# Pico_36Pin_Keyboard.net
KiCad netlist of a schematic drawn in EAGLE
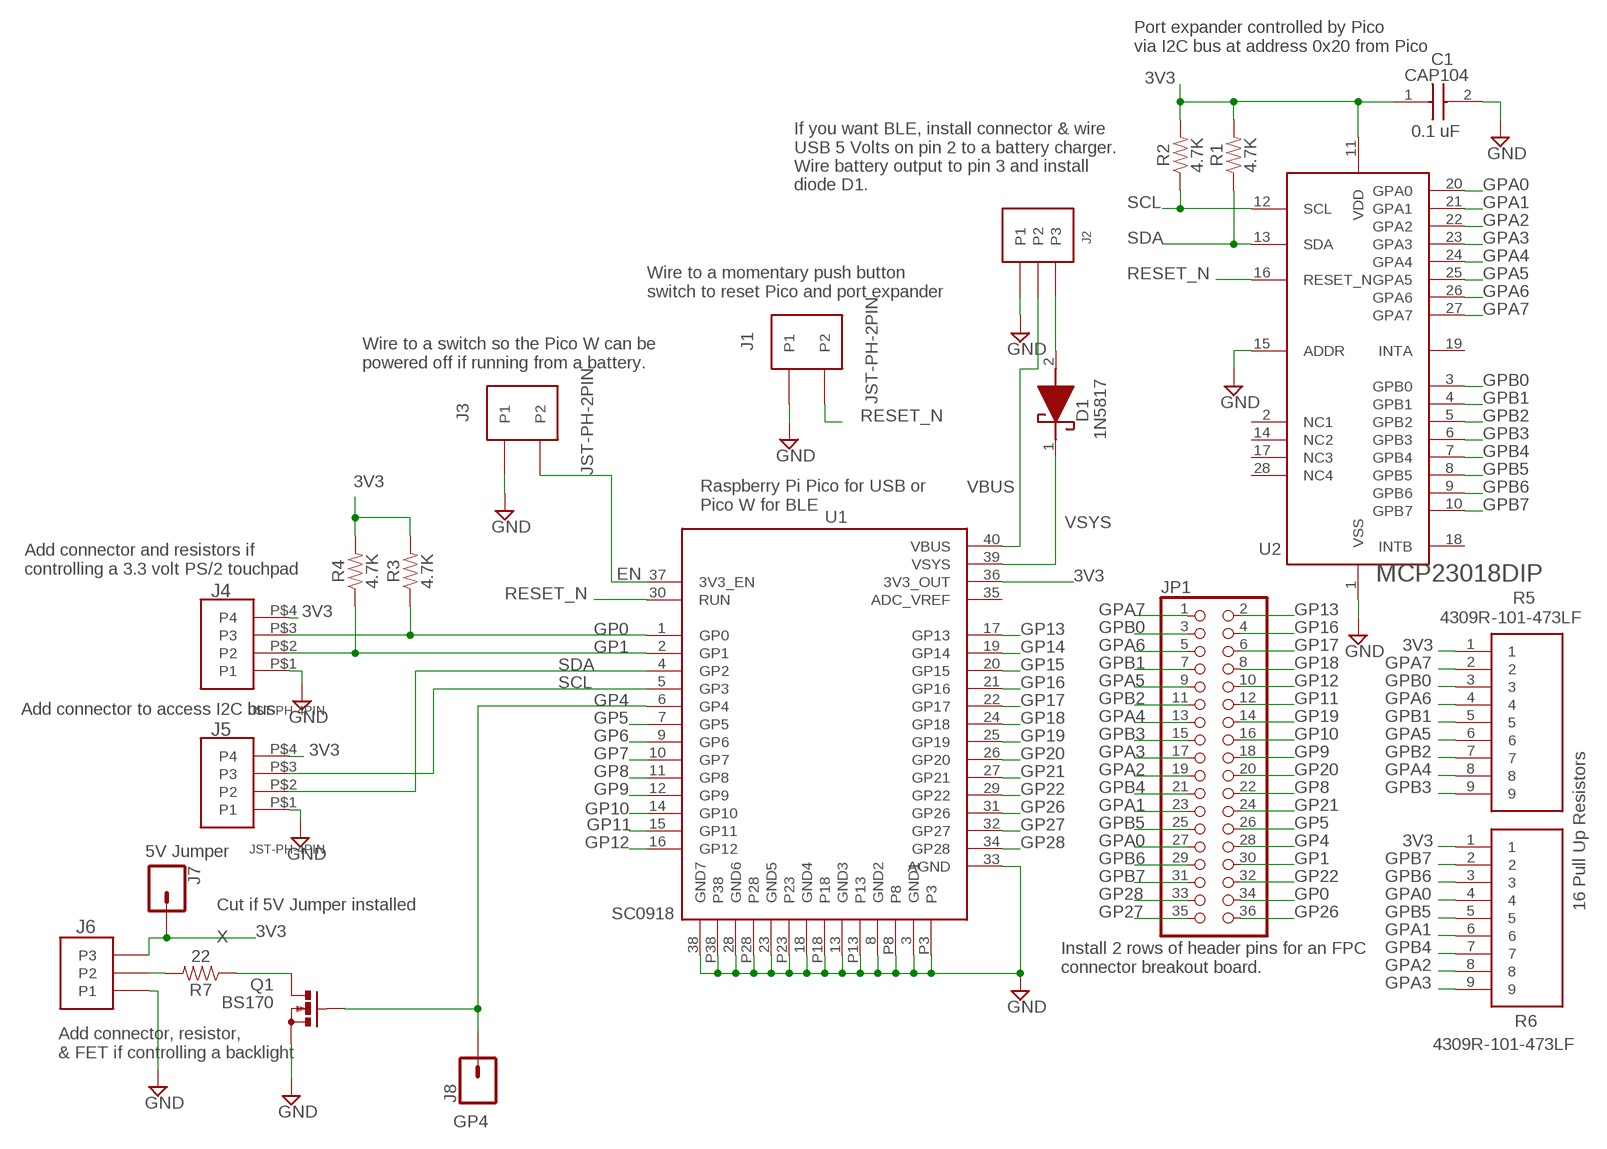
[diagram p0: schematic, sheet 1]

(export (version "E")
  (design (tool "Eeschema 10.0.6"))
  (components
    (comp (ref "C1")
      (value "CAP104")
      (footprint "eagle-import:CAP104")
      (libsource (lib "eagle-import") (part "CAP104"))
    )
    (comp (ref "D1")
      (value "1N5817")
      (footprint "eagle-import:DIOAD1410W86L470D235")
      (fields (field (name "MOUSER_PART_NUMBER") "821-1N5817"))
      (libsource (lib "eagle-import") (part "1N5817"))
    )
    (comp (ref "J1")
      (value "JST-PH-2PIN")
      (footprint "eagle-import:JST-PH-2PIN")
      (libsource (lib "eagle-import") (part "JST-PH-2PIN"))
    )
    (comp (ref "J2")
      (value "JST-PH-3PIN")
      (footprint "eagle-import:JST-PH-3PIN")
      (libsource (lib "eagle-import") (part "JST-PH-3PIN"))
    )
    (comp (ref "J3")
      (value "JST-PH-2PIN")
      (footprint "eagle-import:JST-PH-2PIN")
      (libsource (lib "eagle-import") (part "JST-PH-2PIN"))
    )
    (comp (ref "J4")
      (value "JST-PH-4PIN")
      (footprint "eagle-import:JST-PH-4PIN")
      (libsource (lib "eagle-import") (part "JST-PH-4PIN"))
    )
    (comp (ref "J5")
      (value "JST-PH-4PIN")
      (footprint "eagle-import:JST-PH-4PIN")
      (libsource (lib "eagle-import") (part "JST-PH-4PIN"))
    )
    (comp (ref "J6")
      (value "JST-PH-3PIN")
      (footprint "eagle-import:JST-PH-3PIN")
      (libsource (lib "eagle-import") (part "JST-PH-3PIN"))
    )
    (comp (ref "J7")
      (value "CONN_01")
      (footprint "eagle-import:1X01")
      (libsource (lib "eagle-import") (part "CONN_01"))
    )
    (comp (ref "J8")
      (value "CONN_01")
      (footprint "eagle-import:1X01")
      (libsource (lib "eagle-import") (part "CONN_01"))
    )
    (comp (ref "JP1")
      (value "PINHD-2X18")
      (footprint "eagle-import:2X18")
      (libsource (lib "eagle-import") (part "PINHD-2X18"))
    )
    (comp (ref "Q1")
      (value "BS170")
      (footprint "eagle-import:SOT54E")
      (libsource (lib "eagle-import") (part "BS170"))
    )
    (comp (ref "R1")
      (value "4.7K")
      (footprint "eagle-import:AXIAL-0.3")
      (libsource (lib "eagle-import") (part "RESISTOR_AXIAL"))
    )
    (comp (ref "R2")
      (value "4.7K")
      (footprint "eagle-import:AXIAL-0.3")
      (libsource (lib "eagle-import") (part "RESISTOR_AXIAL"))
    )
    (comp (ref "R3")
      (value "4.7K")
      (footprint "eagle-import:AXIAL-0.3")
      (libsource (lib "eagle-import") (part "RESISTOR_AXIAL"))
    )
    (comp (ref "R4")
      (value "4.7K")
      (footprint "eagle-import:AXIAL-0.3")
      (libsource (lib "eagle-import") (part "RESISTOR_AXIAL"))
    )
    (comp (ref "R5")
      (value "4309R-101-473LF")
      (footprint "eagle-import:4309R-101-473LF")
      (libsource (lib "eagle-import") (part "4309R-101-473LF"))
    )
    (comp (ref "R6")
      (value "4309R-101-473LF")
      (footprint "eagle-import:4309R-101-473LF")
      (libsource (lib "eagle-import") (part "4309R-101-473LF"))
    )
    (comp (ref "R7")
      (value "22")
      (footprint "eagle-import:AXIAL-0.3")
      (libsource (lib "eagle-import") (part "RESISTOR_AXIAL"))
    )
    (comp (ref "U1")
      (value "SC0918")
      (footprint "eagle-import:MODULE_SC0918")
      (fields (field (name "MF") "Raspberry Pi"))
      (libsource (lib "eagle-import") (part "SC0918"))
    )
    (comp (ref "U2")
      (value "MCP23018DIP")
      (footprint "eagle-import:MCP23018DIP")
      (libsource (lib "eagle-import") (part "MCP23018DIP"))
    )
  )
  (nets
    (net (code "1") (name "/3V3") (class "Default")
      (node (ref "C1") (pin "1") (pinfunction "1_1") (pintype "bidirectional"))
      (node (ref "J4") (pin "P$4") (pinfunction "P4_P$4") (pintype "bidirectional"))
      (node (ref "J5") (pin "P$4") (pinfunction "P4_P$4") (pintype "bidirectional"))
      (node (ref "J6") (pin "P$3") (pinfunction "P3_P$3") (pintype "bidirectional"))
      (node (ref "J7") (pin "1") (pinfunction "1_1") (pintype "passive"))
      (node (ref "R1") (pin "P$2") (pinfunction "2_P$2") (pintype "passive"))
      (node (ref "R2") (pin "P$2") (pinfunction "2_P$2") (pintype "passive"))
      (node (ref "R3") (pin "P$2") (pinfunction "2_P$2") (pintype "passive"))
      (node (ref "R4") (pin "P$2") (pinfunction "2_P$2") (pintype "passive"))
      (node (ref "R5") (pin "1") (pinfunction "1_1") (pintype "bidirectional"))
      (node (ref "R6") (pin "1") (pinfunction "1_1") (pintype "bidirectional"))
      (node (ref "U1") (pin "36") (pinfunction "3V3_OUT_36") (pintype "power_in"))
      (node (ref "U2") (pin "11") (pinfunction "VDD_11") (pintype "bidirectional"))
    )
    (net (code "2") (name "/ADC_VREF") (class "Default")
      (node (ref "U1") (pin "35") (pinfunction "ADC_VREF_35") (pintype "power_in"))
    )
    (net (code "3") (name "/EN") (class "Default")
      (node (ref "J3") (pin "P$2") (pinfunction "P2_P$2") (pintype "bidirectional"))
      (node (ref "U1") (pin "37") (pinfunction "3V3_EN_37") (pintype "input"))
    )
    (net (code "4") (name "/GP0") (class "Default")
      (node (ref "J4") (pin "P$3") (pinfunction "P3_P$3") (pintype "bidirectional"))
      (node (ref "JP1") (pin "34") (pinfunction "34_34") (pintype "passive"))
      (node (ref "R3") (pin "P$1") (pinfunction "1_P$1") (pintype "passive"))
      (node (ref "U1") (pin "1") (pinfunction "GP0_1") (pintype "bidirectional"))
    )
    (net (code "5") (name "/GP1") (class "Default")
      (node (ref "J4") (pin "P$2") (pinfunction "P2_P$2") (pintype "bidirectional"))
      (node (ref "JP1") (pin "30") (pinfunction "30_30") (pintype "passive"))
      (node (ref "R4") (pin "P$1") (pinfunction "1_P$1") (pintype "passive"))
      (node (ref "U1") (pin "2") (pinfunction "GP1_2") (pintype "bidirectional"))
    )
    (net (code "6") (name "/GP4") (class "Default")
      (node (ref "J8") (pin "1") (pinfunction "1_1") (pintype "passive"))
      (node (ref "JP1") (pin "28") (pinfunction "28_28") (pintype "passive"))
      (node (ref "Q1") (pin "G") (pinfunction "G_G") (pintype "passive"))
      (node (ref "U1") (pin "6") (pinfunction "GP4_6") (pintype "bidirectional"))
    )
    (net (code "7") (name "/GP5") (class "Default")
      (node (ref "JP1") (pin "26") (pinfunction "26_26") (pintype "passive"))
      (node (ref "U1") (pin "7") (pinfunction "GP5_7") (pintype "bidirectional"))
    )
    (net (code "8") (name "/GP6") (class "Default")
      (node (ref "U1") (pin "9") (pinfunction "GP6_9") (pintype "bidirectional"))
    )
    (net (code "9") (name "/GP7") (class "Default")
      (node (ref "U1") (pin "10") (pinfunction "GP7_10") (pintype "bidirectional"))
    )
    (net (code "10") (name "/GP8") (class "Default")
      (node (ref "JP1") (pin "22") (pinfunction "22_22") (pintype "passive"))
      (node (ref "U1") (pin "11") (pinfunction "GP8_11") (pintype "bidirectional"))
    )
    (net (code "11") (name "/GP9") (class "Default")
      (node (ref "JP1") (pin "18") (pinfunction "18_18") (pintype "passive"))
      (node (ref "U1") (pin "12") (pinfunction "GP9_12") (pintype "bidirectional"))
    )
    (net (code "12") (name "/GP10") (class "Default")
      (node (ref "JP1") (pin "16") (pinfunction "16_16") (pintype "passive"))
      (node (ref "U1") (pin "14") (pinfunction "GP10_14") (pintype "bidirectional"))
    )
    (net (code "13") (name "/GP11") (class "Default")
      (node (ref "JP1") (pin "12") (pinfunction "12_12") (pintype "passive"))
      (node (ref "U1") (pin "15") (pinfunction "GP11_15") (pintype "bidirectional"))
    )
    (net (code "14") (name "/GP12") (class "Default")
      (node (ref "JP1") (pin "10") (pinfunction "10_10") (pintype "passive"))
      (node (ref "U1") (pin "16") (pinfunction "GP12_16") (pintype "bidirectional"))
    )
    (net (code "15") (name "/GP13") (class "Default")
      (node (ref "JP1") (pin "2") (pinfunction "2_2") (pintype "passive"))
      (node (ref "U1") (pin "17") (pinfunction "GP13_17") (pintype "bidirectional"))
    )
    (net (code "16") (name "/GP14") (class "Default")
      (node (ref "U1") (pin "19") (pinfunction "GP14_19") (pintype "bidirectional"))
    )
    (net (code "17") (name "/GP15") (class "Default")
      (node (ref "U1") (pin "20") (pinfunction "GP15_20") (pintype "bidirectional"))
    )
    (net (code "18") (name "/GP16") (class "Default")
      (node (ref "JP1") (pin "4") (pinfunction "4_4") (pintype "passive"))
      (node (ref "U1") (pin "21") (pinfunction "GP16_21") (pintype "bidirectional"))
    )
    (net (code "19") (name "/GP17") (class "Default")
      (node (ref "JP1") (pin "6") (pinfunction "6_6") (pintype "passive"))
      (node (ref "U1") (pin "22") (pinfunction "GP17_22") (pintype "bidirectional"))
    )
    (net (code "20") (name "/GP18") (class "Default")
      (node (ref "JP1") (pin "8") (pinfunction "8_8") (pintype "passive"))
      (node (ref "U1") (pin "24") (pinfunction "GP18_24") (pintype "bidirectional"))
    )
    (net (code "21") (name "/GP19") (class "Default")
      (node (ref "JP1") (pin "14") (pinfunction "14_14") (pintype "passive"))
      (node (ref "U1") (pin "25") (pinfunction "GP19_25") (pintype "bidirectional"))
    )
    (net (code "22") (name "/GP20") (class "Default")
      (node (ref "JP1") (pin "20") (pinfunction "20_20") (pintype "passive"))
      (node (ref "U1") (pin "26") (pinfunction "GP20_26") (pintype "bidirectional"))
    )
    (net (code "23") (name "/GP21") (class "Default")
      (node (ref "JP1") (pin "24") (pinfunction "24_24") (pintype "passive"))
      (node (ref "U1") (pin "27") (pinfunction "GP21_27") (pintype "bidirectional"))
    )
    (net (code "24") (name "/GP22") (class "Default")
      (node (ref "JP1") (pin "32") (pinfunction "32_32") (pintype "passive"))
      (node (ref "U1") (pin "29") (pinfunction "GP22_29") (pintype "bidirectional"))
    )
    (net (code "25") (name "/GP26") (class "Default")
      (node (ref "JP1") (pin "36") (pinfunction "36_36") (pintype "passive"))
      (node (ref "U1") (pin "31") (pinfunction "GP26_31") (pintype "bidirectional"))
    )
    (net (code "26") (name "/GP27") (class "Default")
      (node (ref "JP1") (pin "35") (pinfunction "35_35") (pintype "passive"))
      (node (ref "U1") (pin "32") (pinfunction "GP27_32") (pintype "bidirectional"))
    )
    (net (code "27") (name "/GP28") (class "Default")
      (node (ref "JP1") (pin "33") (pinfunction "33_33") (pintype "passive"))
      (node (ref "U1") (pin "34") (pinfunction "GP28_34") (pintype "bidirectional"))
    )
    (net (code "28") (name "/GPA0") (class "Default")
      (node (ref "JP1") (pin "27") (pinfunction "27_27") (pintype "passive"))
      (node (ref "R6") (pin "4") (pinfunction "4_4") (pintype "bidirectional"))
      (node (ref "U2") (pin "20") (pinfunction "GPA0_20") (pintype "bidirectional"))
    )
    (net (code "29") (name "/GPA1") (class "Default")
      (node (ref "JP1") (pin "23") (pinfunction "23_23") (pintype "passive"))
      (node (ref "R6") (pin "6") (pinfunction "6_6") (pintype "bidirectional"))
      (node (ref "U2") (pin "21") (pinfunction "GPA1_21") (pintype "bidirectional"))
    )
    (net (code "30") (name "/GPA2") (class "Default")
      (node (ref "JP1") (pin "19") (pinfunction "19_19") (pintype "passive"))
      (node (ref "R6") (pin "8") (pinfunction "8_8") (pintype "bidirectional"))
      (node (ref "U2") (pin "22") (pinfunction "GPA2_22") (pintype "bidirectional"))
    )
    (net (code "31") (name "/GPA3") (class "Default")
      (node (ref "JP1") (pin "17") (pinfunction "17_17") (pintype "passive"))
      (node (ref "R6") (pin "9") (pinfunction "9_9") (pintype "bidirectional"))
      (node (ref "U2") (pin "23") (pinfunction "GPA3_23") (pintype "bidirectional"))
    )
    (net (code "32") (name "/GPA4") (class "Default")
      (node (ref "JP1") (pin "13") (pinfunction "13_13") (pintype "passive"))
      (node (ref "R5") (pin "8") (pinfunction "8_8") (pintype "bidirectional"))
      (node (ref "U2") (pin "24") (pinfunction "GPA4_24") (pintype "bidirectional"))
    )
    (net (code "33") (name "/GPA5") (class "Default")
      (node (ref "JP1") (pin "9") (pinfunction "9_9") (pintype "passive"))
      (node (ref "R5") (pin "6") (pinfunction "6_6") (pintype "bidirectional"))
      (node (ref "U2") (pin "25") (pinfunction "GPA5_25") (pintype "bidirectional"))
    )
    (net (code "34") (name "/GPA6") (class "Default")
      (node (ref "JP1") (pin "5") (pinfunction "5_5") (pintype "passive"))
      (node (ref "R5") (pin "4") (pinfunction "4_4") (pintype "bidirectional"))
      (node (ref "U2") (pin "26") (pinfunction "GPA6_26") (pintype "bidirectional"))
    )
    (net (code "35") (name "/GPA7") (class "Default")
      (node (ref "JP1") (pin "1") (pinfunction "1_1") (pintype "passive"))
      (node (ref "R5") (pin "2") (pinfunction "2_2") (pintype "bidirectional"))
      (node (ref "U2") (pin "27") (pinfunction "GPA7_27") (pintype "bidirectional"))
    )
    (net (code "36") (name "/GPB0") (class "Default")
      (node (ref "JP1") (pin "3") (pinfunction "3_3") (pintype "passive"))
      (node (ref "R5") (pin "3") (pinfunction "3_3") (pintype "bidirectional"))
      (node (ref "U2") (pin "3") (pinfunction "GPB0_3") (pintype "bidirectional"))
    )
    (net (code "37") (name "/GPB1") (class "Default")
      (node (ref "JP1") (pin "7") (pinfunction "7_7") (pintype "passive"))
      (node (ref "R5") (pin "5") (pinfunction "5_5") (pintype "bidirectional"))
      (node (ref "U2") (pin "4") (pinfunction "GPB1_4") (pintype "bidirectional"))
    )
    (net (code "38") (name "/GPB2") (class "Default")
      (node (ref "JP1") (pin "11") (pinfunction "11_11") (pintype "passive"))
      (node (ref "R5") (pin "7") (pinfunction "7_7") (pintype "bidirectional"))
      (node (ref "U2") (pin "5") (pinfunction "GPB2_5") (pintype "bidirectional"))
    )
    (net (code "39") (name "/GPB3") (class "Default")
      (node (ref "JP1") (pin "15") (pinfunction "15_15") (pintype "passive"))
      (node (ref "R5") (pin "9") (pinfunction "9_9") (pintype "bidirectional"))
      (node (ref "U2") (pin "6") (pinfunction "GPB3_6") (pintype "bidirectional"))
    )
    (net (code "40") (name "/GPB4") (class "Default")
      (node (ref "JP1") (pin "21") (pinfunction "21_21") (pintype "passive"))
      (node (ref "R6") (pin "7") (pinfunction "7_7") (pintype "bidirectional"))
      (node (ref "U2") (pin "7") (pinfunction "GPB4_7") (pintype "bidirectional"))
    )
    (net (code "41") (name "/GPB5") (class "Default")
      (node (ref "JP1") (pin "25") (pinfunction "25_25") (pintype "passive"))
      (node (ref "R6") (pin "5") (pinfunction "5_5") (pintype "bidirectional"))
      (node (ref "U2") (pin "8") (pinfunction "GPB5_8") (pintype "bidirectional"))
    )
    (net (code "42") (name "/GPB6") (class "Default")
      (node (ref "JP1") (pin "29") (pinfunction "29_29") (pintype "passive"))
      (node (ref "R6") (pin "3") (pinfunction "3_3") (pintype "bidirectional"))
      (node (ref "U2") (pin "9") (pinfunction "GPB6_9") (pintype "bidirectional"))
    )
    (net (code "43") (name "/GPB7") (class "Default")
      (node (ref "JP1") (pin "31") (pinfunction "31_31") (pintype "passive"))
      (node (ref "R6") (pin "2") (pinfunction "2_2") (pintype "bidirectional"))
      (node (ref "U2") (pin "10") (pinfunction "GPB7_10") (pintype "bidirectional"))
    )
    (net (code "44") (name "/RESET_N") (class "Default")
      (node (ref "J1") (pin "P$2") (pinfunction "P2_P$2") (pintype "bidirectional"))
      (node (ref "U1") (pin "30") (pinfunction "RUN_30") (pintype "input"))
      (node (ref "U2") (pin "16") (pinfunction "RESET_N_16") (pintype "bidirectional"))
    )
    (net (code "45") (name "/SCL") (class "Default")
      (node (ref "J5") (pin "P$3") (pinfunction "P3_P$3") (pintype "bidirectional"))
      (node (ref "R2") (pin "P$1") (pinfunction "1_P$1") (pintype "passive"))
      (node (ref "U1") (pin "5") (pinfunction "GP3_5") (pintype "bidirectional"))
      (node (ref "U2") (pin "12") (pinfunction "SCL_12") (pintype "bidirectional"))
    )
    (net (code "46") (name "/SDA") (class "Default")
      (node (ref "J5") (pin "P$2") (pinfunction "P2_P$2") (pintype "bidirectional"))
      (node (ref "R1") (pin "P$1") (pinfunction "1_P$1") (pintype "passive"))
      (node (ref "U1") (pin "4") (pinfunction "GP2_4") (pintype "bidirectional"))
      (node (ref "U2") (pin "13") (pinfunction "SDA_13") (pintype "bidirectional"))
    )
    (net (code "47") (name "/VBUS") (class "Default")
      (node (ref "J2") (pin "P$2") (pinfunction "P2_P$2") (pintype "bidirectional"))
      (node (ref "U1") (pin "40") (pinfunction "VBUS_40") (pintype "power_in"))
    )
    (net (code "48") (name "/VSYS") (class "Default")
      (node (ref "D1") (pin "1") (pinfunction "K_1") (pintype "bidirectional"))
      (node (ref "U1") (pin "39") (pinfunction "VSYS_39") (pintype "power_in"))
    )
    (net (code "49") (name "GND") (class "Default")
      (node (ref "C1") (pin "2") (pinfunction "2_2") (pintype "bidirectional"))
      (node (ref "J1") (pin "P$1") (pinfunction "P1_P$1") (pintype "bidirectional"))
      (node (ref "J2") (pin "P$1") (pinfunction "P1_P$1") (pintype "bidirectional"))
      (node (ref "J3") (pin "P$1") (pinfunction "P1_P$1") (pintype "bidirectional"))
      (node (ref "J4") (pin "P$1") (pinfunction "P1_P$1") (pintype "bidirectional"))
      (node (ref "J5") (pin "P$1") (pinfunction "P1_P$1") (pintype "bidirectional"))
      (node (ref "J6") (pin "P$1") (pinfunction "P1_P$1") (pintype "bidirectional"))
      (node (ref "Q1") (pin "S") (pinfunction "S_S") (pintype "passive"))
      (node (ref "U1") (pin "13") (pinfunction "GND3_13") (pintype "power_in"))
      (node (ref "U1") (pin "18") (pinfunction "GND4_18") (pintype "power_in"))
      (node (ref "U1") (pin "23") (pinfunction "GND5_23") (pintype "power_in"))
      (node (ref "U1") (pin "28") (pinfunction "GND6_28") (pintype "power_in"))
      (node (ref "U1") (pin "3") (pinfunction "GND1_3") (pintype "power_in"))
      (node (ref "U1") (pin "33") (pinfunction "AGND_33") (pintype "power_in"))
      (node (ref "U1") (pin "38") (pinfunction "GND7_38") (pintype "power_in"))
      (node (ref "U1") (pin "8") (pinfunction "GND2_8") (pintype "power_in"))
      (node (ref "U1") (pin "P13") (pinfunction "P13_P13") (pintype "power_in"))
      (node (ref "U1") (pin "P18") (pinfunction "P18_P18") (pintype "power_in"))
      (node (ref "U1") (pin "P23") (pinfunction "P23_P23") (pintype "power_in"))
      (node (ref "U1") (pin "P28") (pinfunction "P28_P28") (pintype "power_in"))
      (node (ref "U1") (pin "P3") (pinfunction "P3_P3") (pintype "power_in"))
      (node (ref "U1") (pin "P38") (pinfunction "P38_P38") (pintype "power_in"))
      (node (ref "U1") (pin "P8") (pinfunction "P8_P8") (pintype "power_in"))
      (node (ref "U2") (pin "1") (pinfunction "VSS_1") (pintype "bidirectional"))
      (node (ref "U2") (pin "15") (pinfunction "ADDR_15") (pintype "bidirectional"))
    )
    (net (code "50") (name "Net-(D1-A)") (class "Default")
      (node (ref "D1") (pin "2") (pinfunction "A_2") (pintype "bidirectional"))
      (node (ref "J2") (pin "P$3") (pinfunction "P3_P$3") (pintype "bidirectional"))
    )
    (net (code "51") (name "Net-(J6-P2)") (class "Default")
      (node (ref "J6") (pin "P$2") (pinfunction "P2_P$2") (pintype "bidirectional"))
      (node (ref "R7") (pin "P$2") (pinfunction "2_P$2") (pintype "passive"))
    )
    (net (code "52") (name "Net-(R7-1)") (class "Default")
      (node (ref "Q1") (pin "D") (pinfunction "D_D") (pintype "passive"))
      (node (ref "R7") (pin "P$1") (pinfunction "1_P$1") (pintype "passive"))
    )
    (net (code "53") (name "unconnected-(U2-INTA-Pad19)") (class "Default")
      (node (ref "U2") (pin "19") (pinfunction "INTA_19") (pintype "bidirectional"))
    )
    (net (code "54") (name "unconnected-(U2-INTB-Pad18)") (class "Default")
      (node (ref "U2") (pin "18") (pinfunction "INTB_18") (pintype "bidirectional"))
    )
    (net (code "55") (name "unconnected-(U2-NC1-Pad2)") (class "Default")
      (node (ref "U2") (pin "2") (pinfunction "NC1_2") (pintype "bidirectional"))
    )
    (net (code "56") (name "unconnected-(U2-NC2-Pad14)") (class "Default")
      (node (ref "U2") (pin "14") (pinfunction "NC2_14") (pintype "bidirectional"))
    )
    (net (code "57") (name "unconnected-(U2-NC3-Pad17)") (class "Default")
      (node (ref "U2") (pin "17") (pinfunction "NC3_17") (pintype "bidirectional"))
    )
    (net (code "58") (name "unconnected-(U2-NC4-Pad28)") (class "Default")
      (node (ref "U2") (pin "28") (pinfunction "NC4_28") (pintype "bidirectional"))
    )
  )
)
